# LAB-02.net
KiCad netlist of a schematic drawn in Altium Designer
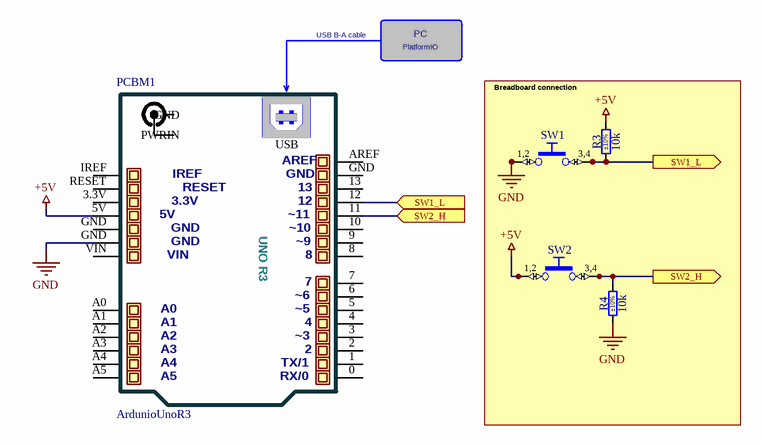
[diagram p0: LAB-02.SchDoc]

(export (version "E")
  (design (tool "Eeschema 10.0.6"))
  (components
    (comp (ref "PCBM1")
      (value "ArdunioUnoR3")
      (description "ArdunioUnoR3 Universal SCH Symbol \r\n(C) 230232")
      (libsource (lib "ArduinoUnoR3") (part "ArdunioUnoR3"))
    )
    (comp (ref "R3")
      (value "10k")
      (footprint "RESC3216X65N")
      (description "Resistor - 0.1%")
      (fields
        (field (name "TOLERANCE") "±10%")
        (field (name "PART NUMBER") "R1206_270R_0.1%_0.25W_25PPM")
        (field (name "POWER") "0.25W")
        (field (name "AUTHOR") "CERN DEM JLC")
      )
      (libsource (lib "Resistors") (part "Resistor - 0.1%"))
    )
    (comp (ref "R4")
      (value "10k")
      (footprint "RESC3216X65N")
      (description "Resistor - 0.1%")
      (fields
        (field (name "TOLERANCE") "±10%")
        (field (name "PART NUMBER") "R1206_270R_0.1%_0.25W_25PPM")
        (field (name "POWER") "0.25W")
        (field (name "AUTHOR") "CERN DEM JLC")
      )
      (libsource (lib "Resistors") (part "Resistor - 0.1%"))
    )
    (comp (ref "SW1")
      (value "Push Button")
      (footprint "PB_ALPS_SKHHDTA010")
      (description "Push-Button Switch SPDT")
      (fields
        (field (name "PART NUMBER") "PB_ALPS_SKHHDTA010")
        (field (name "MANUFACTURER") "ALPS")
        (field (name "AUTHOR") "CERN DEM JLC")
      )
      (libsource (lib "Eletro-mechanical") (part "PB SPST 12NO-34NO"))
    )
    (comp (ref "SW2")
      (value "Push Button")
      (footprint "PB_ALPS_SKHHDTA010")
      (description "Push-Button Switch SPDT")
      (fields
        (field (name "PART NUMBER") "PB_ALPS_SKHHDTA010")
        (field (name "MANUFACTURER") "ALPS")
        (field (name "AUTHOR") "CERN DEM JLC")
      )
      (libsource (lib "Eletro-mechanical") (part "PB SPST 12NO-34NO"))
    )
  )
  (nets
    (net (code "1") (name "+5V") (class "Default")
      (node (ref "PCBM1") (pin "5V") (pinfunction "5V_5V") (pintype "passive"))
      (node (ref "R3") (pin "2") (pinfunction "2_2") (pintype "passive"))
      (node (ref "SW2") (pin "1") (pinfunction "1_1") (pintype "bidirectional"))
      (node (ref "SW2") (pin "2") (pinfunction "2_2") (pintype "bidirectional"))
    )
    (net (code "2") (name "/SW1_L") (class "Default")
      (node (ref "PCBM1") (pin "12") (pinfunction "12_12") (pintype "passive"))
      (node (ref "R3") (pin "1") (pinfunction "1_1") (pintype "passive"))
      (node (ref "SW1") (pin "3") (pinfunction "3_3") (pintype "bidirectional"))
      (node (ref "SW1") (pin "4") (pinfunction "4_4") (pintype "bidirectional"))
    )
    (net (code "3") (name "/SW2_H") (class "Default")
      (node (ref "PCBM1") (pin "11") (pinfunction "11_11") (pintype "passive"))
      (node (ref "R4") (pin "2") (pinfunction "2_2") (pintype "passive"))
      (node (ref "SW2") (pin "3") (pinfunction "3_3") (pintype "bidirectional"))
      (node (ref "SW2") (pin "4") (pinfunction "4_4") (pintype "bidirectional"))
    )
    (net (code "4") (name "GND") (class "Default")
      (node (ref "PCBM1") (pin "GND") (pinfunction "GND_GND") (pintype "passive"))
      (node (ref "R4") (pin "1") (pinfunction "1_1") (pintype "passive"))
      (node (ref "SW1") (pin "1") (pinfunction "1_1") (pintype "bidirectional"))
      (node (ref "SW1") (pin "2") (pinfunction "2_2") (pintype "bidirectional"))
    )
    (net (code "5") (name "unconnected-(PCBM1-Pad0)") (class "Default")
      (node (ref "PCBM1") (pin "0") (pinfunction "0_0") (pintype "passive"))
    )
    (net (code "6") (name "unconnected-(PCBM1-Pad1)") (class "Default")
      (node (ref "PCBM1") (pin "1") (pinfunction "1_1") (pintype "passive"))
    )
    (net (code "7") (name "unconnected-(PCBM1-Pad2)") (class "Default")
      (node (ref "PCBM1") (pin "2") (pinfunction "2_2") (pintype "passive"))
    )
    (net (code "8") (name "unconnected-(PCBM1-Pad3)") (class "Default")
      (node (ref "PCBM1") (pin "3") (pinfunction "3_3") (pintype "passive"))
    )
    (net (code "9") (name "unconnected-(PCBM1-Pad3.3V)") (class "Default")
      (node (ref "PCBM1") (pin "3.3V") (pinfunction "3.3V_3.3V") (pintype "passive"))
    )
    (net (code "10") (name "unconnected-(PCBM1-Pad4)") (class "Default")
      (node (ref "PCBM1") (pin "4") (pinfunction "4_4") (pintype "passive"))
    )
    (net (code "11") (name "unconnected-(PCBM1-Pad5)") (class "Default")
      (node (ref "PCBM1") (pin "5") (pinfunction "5_5") (pintype "passive"))
    )
    (net (code "12") (name "unconnected-(PCBM1-Pad6)") (class "Default")
      (node (ref "PCBM1") (pin "6") (pinfunction "6_6") (pintype "passive"))
    )
    (net (code "13") (name "unconnected-(PCBM1-Pad7)") (class "Default")
      (node (ref "PCBM1") (pin "7") (pinfunction "7_7") (pintype "passive"))
    )
    (net (code "14") (name "unconnected-(PCBM1-Pad8)") (class "Default")
      (node (ref "PCBM1") (pin "8") (pinfunction "8_8") (pintype "passive"))
    )
    (net (code "15") (name "unconnected-(PCBM1-Pad9)") (class "Default")
      (node (ref "PCBM1") (pin "9") (pinfunction "9_9") (pintype "passive"))
    )
    (net (code "16") (name "unconnected-(PCBM1-Pad10)") (class "Default")
      (node (ref "PCBM1") (pin "10") (pinfunction "10_10") (pintype "passive"))
    )
    (net (code "17") (name "unconnected-(PCBM1-Pad13)") (class "Default")
      (node (ref "PCBM1") (pin "13") (pinfunction "13_13") (pintype "passive"))
    )
    (net (code "18") (name "unconnected-(PCBM1-PadA0)") (class "Default")
      (node (ref "PCBM1") (pin "A0") (pinfunction "A0_A0") (pintype "passive"))
    )
    (net (code "19") (name "unconnected-(PCBM1-PadA1)") (class "Default")
      (node (ref "PCBM1") (pin "A1") (pinfunction "A1_A1") (pintype "passive"))
    )
    (net (code "20") (name "unconnected-(PCBM1-PadA2)") (class "Default")
      (node (ref "PCBM1") (pin "A2") (pinfunction "A2_A2") (pintype "passive"))
    )
    (net (code "21") (name "unconnected-(PCBM1-PadA3)") (class "Default")
      (node (ref "PCBM1") (pin "A3") (pinfunction "A3_A3") (pintype "passive"))
    )
    (net (code "22") (name "unconnected-(PCBM1-PadA4)") (class "Default")
      (node (ref "PCBM1") (pin "A4") (pinfunction "A4_A4") (pintype "passive"))
    )
    (net (code "23") (name "unconnected-(PCBM1-PadA5)") (class "Default")
      (node (ref "PCBM1") (pin "A5") (pinfunction "A5_A5") (pintype "passive"))
    )
    (net (code "24") (name "unconnected-(PCBM1-PadAREF)") (class "Default")
      (node (ref "PCBM1") (pin "AREF") (pinfunction "AREF_AREF") (pintype "passive"))
    )
    (net (code "25") (name "unconnected-(PCBM1-PadGND)") (class "Default")
      (node (ref "PCBM1") (pin "GND") (pinfunction "GND_GND") (pintype "passive"))
    )
    (net (code "26") (name "unconnected-(PCBM1-PadGND)_1") (class "Default")
      (node (ref "PCBM1") (pin "GND") (pinfunction "GND_GND") (pintype "passive"))
    )
    (net (code "27") (name "unconnected-(PCBM1-PadIREF)") (class "Default")
      (node (ref "PCBM1") (pin "IREF") (pinfunction "IREF_IREF") (pintype "passive"))
    )
    (net (code "28") (name "unconnected-(PCBM1-PadRESET)") (class "Default")
      (node (ref "PCBM1") (pin "RESET") (pinfunction "RESET_RESET") (pintype "passive"))
    )
    (net (code "29") (name "unconnected-(PCBM1-PadVIN)") (class "Default")
      (node (ref "PCBM1") (pin "VIN") (pinfunction "VIN_VIN") (pintype "passive"))
    )
  )
)
